# kanal.net
KiCad netlist of a schematic drawn in Altium Designer
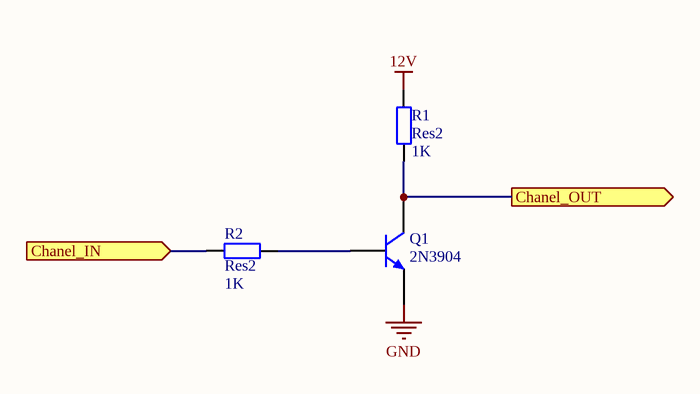
[diagram p0: kanal.SchDoc]

(export (version "E")
  (design (tool "Eeschema 10.0.6"))
  (components
    (comp (ref "Q1")
      (value "2N3904")
      (footprint "TO-92A")
      (description "NPN General Purpose Amplifier")
      (fields (field (name "PUBLISHER") "Altium Limited"))
      (libsource (lib "Miscellaneous Devices") (part "2N3904"))
    )
    (comp (ref "R1")
      (value "Res2")
      (footprint "AXIAL-0.4")
      (description "Resistor")
      (fields (field (name "ALTIUM_VALUE") "1K") (field (name "PUBLISHER") "Altium Limited"))
      (libsource (lib "Miscellaneous Devices") (part "Res2"))
    )
    (comp (ref "R2")
      (value "Res2")
      (footprint "AXIAL-0.4")
      (description "Resistor")
      (fields (field (name "ALTIUM_VALUE") "1K") (field (name "PUBLISHER") "Altium Limited"))
      (libsource (lib "") (part "Res2_1"))
    )
  )
  (nets
    (net (code "1") (name "/Chanel_IN") (class "Default")
      (node (ref "R2") (pin "1") (pinfunction "1_1") (pintype "passive"))
    )
    (net (code "2") (name "/Chanel_OUT") (class "Default")
      (node (ref "Q1") (pin "3") (pinfunction "C_3") (pintype "passive"))
      (node (ref "R1") (pin "1") (pinfunction "1_1") (pintype "passive"))
    )
    (net (code "3") (name "12V") (class "Default")
      (node (ref "R1") (pin "2") (pinfunction "2_2") (pintype "passive"))
    )
    (net (code "4") (name "GND") (class "Default")
      (node (ref "Q1") (pin "1") (pinfunction "E_1") (pintype "passive"))
    )
    (net (code "5") (name "Net-(Q1-B)") (class "Default")
      (node (ref "Q1") (pin "2") (pinfunction "B_2") (pintype "passive"))
      (node (ref "R2") (pin "2") (pinfunction "2_2") (pintype "passive"))
    )
  )
)
